# Stepper_CANBus_V2.net
KiCad netlist of a schematic drawn in EAGLE
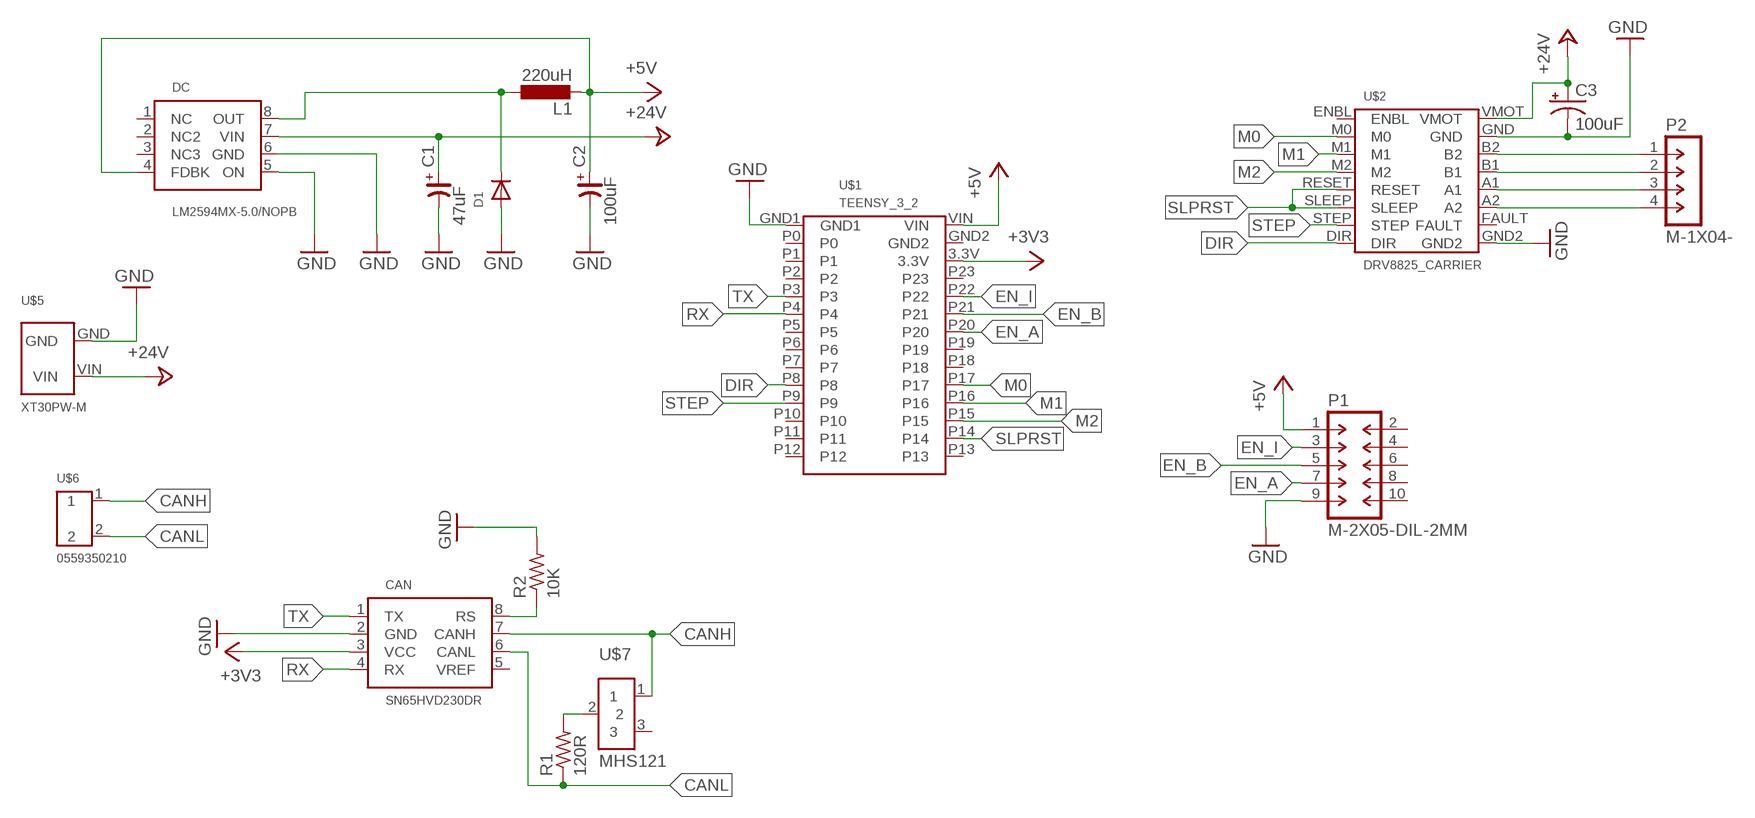
[diagram p0: schematic, sheet 1]

(export (version "E")
  (design (tool "Eeschema 10.0.6"))
  (components
    (comp (ref "C1")
      (value "47uF")
      (footprint "eagle-import:C7343_T")
      (libsource (lib "eagle-import") (part "CP_7343"))
    )
    (comp (ref "C2")
      (value "100uF")
      (footprint "eagle-import:C7343_T")
      (libsource (lib "eagle-import") (part "CP_7343"))
    )
    (comp (ref "C3")
      (value "100uF")
      (footprint "eagle-import:E2,5-7")
      (libsource (lib "eagle-import") (part "CPOL-USE2.5-7"))
    )
    (comp (ref "CAN")
      (value "SN65HVD230DR")
      (footprint "eagle-import:SOIC8")
      (libsource (lib "eagle-import") (part "SN65HVD230DR"))
    )
    (comp (ref "D1")
      (value "DIODESOD-323F")
      (footprint "eagle-import:SOD-323F")
      (libsource (lib "eagle-import") (part "DIODESOD-323F"))
    )
    (comp (ref "DC")
      (value "LM2594MX-5.0/NOPB")
      (footprint "eagle-import:SOIC8")
      (libsource (lib "eagle-import") (part "LM2594MX-5.0/NOPB"))
    )
    (comp (ref "L1")
      (value "220uH")
      (footprint "eagle-import:L4532M")
      (libsource (lib "eagle-import") (part "L-EUL4532C"))
    )
    (comp (ref "P1")
      (value "M-2X05-DIL-2MM")
      (footprint "eagle-import:DIL-2MM-2X05")
      (libsource (lib "eagle-import") (part "M-2X05-DIL-2MM"))
    )
    (comp (ref "P2")
      (value "M-1X04-")
      (footprint "eagle-import:DIL-2MM-1X04")
      (libsource (lib "eagle-import") (part "M-1X04-"))
    )
    (comp (ref "R1")
      (value "120R")
      (footprint "eagle-import:R0603")
      (libsource (lib "eagle-import") (part "R-US_R0603"))
    )
    (comp (ref "R2")
      (value "10K")
      (footprint "eagle-import:R0603")
      (libsource (lib "eagle-import") (part "R-US_R0603"))
    )
    (comp (ref "U$1")
      (value "TEENSY_3_2")
      (footprint "eagle-import:TEENSY_3_2")
      (libsource (lib "eagle-import") (part "TEENSY_3_2"))
    )
    (comp (ref "U$2")
      (value "DRV8825_CARRIER")
      (footprint "eagle-import:DRV8825_CARRIER")
      (libsource (lib "eagle-import") (part "DRV8825_CARRIER"))
    )
    (comp (ref "U$5")
      (value "XT30PW-M")
      (footprint "eagle-import:XT30PW-M")
      (libsource (lib "eagle-import") (part "XT30PW-M"))
    )
    (comp (ref "U$6")
      (value "0559350210")
      (footprint "eagle-import:0559350210")
      (libsource (lib "eagle-import") (part "0559350210"))
    )
    (comp (ref "U$7")
      (value "MHS121")
      (footprint "eagle-import:MHS121")
      (libsource (lib "eagle-import") (part "MHS121"))
    )
  )
  (nets
    (net (code "1") (name "+3V3") (class "Default")
      (node (ref "CAN") (pin "3") (pinfunction "VCC_3") (pintype "bidirectional"))
      (node (ref "U$1") (pin "3.3V") (pinfunction "3.3V_3.3V") (pintype "bidirectional"))
    )
    (net (code "2") (name "+5V") (class "Default")
      (node (ref "C2") (pin "+") (pinfunction "+_+") (pintype "passive"))
      (node (ref "DC") (pin "4") (pinfunction "FDBK_4") (pintype "bidirectional"))
      (node (ref "L1") (pin "2") (pinfunction "2_2") (pintype "passive"))
      (node (ref "P1") (pin "1") (pinfunction "1_1") (pintype "passive"))
      (node (ref "U$1") (pin "VIN") (pinfunction "VIN_VIN") (pintype "bidirectional"))
    )
    (net (code "3") (name "+24V") (class "Default")
      (node (ref "C1") (pin "+") (pinfunction "+_+") (pintype "passive"))
      (node (ref "C3") (pin "+") (pinfunction "+_+") (pintype "passive"))
      (node (ref "DC") (pin "7") (pinfunction "VIN_7") (pintype "bidirectional"))
      (node (ref "U$2") (pin "VMOT") (pinfunction "VMOT_VMOT") (pintype "bidirectional"))
      (node (ref "U$5") (pin "VIN") (pinfunction "VIN_VIN") (pintype "bidirectional"))
    )
    (net (code "4") (name "CANH") (class "Default")
      (node (ref "CAN") (pin "7") (pinfunction "CANH_7") (pintype "bidirectional"))
      (node (ref "U$6") (pin "1") (pinfunction "1_1") (pintype "bidirectional"))
      (node (ref "U$7") (pin "1") (pinfunction "1_1") (pintype "bidirectional"))
    )
    (net (code "5") (name "CANL") (class "Default")
      (node (ref "CAN") (pin "6") (pinfunction "CANL_6") (pintype "bidirectional"))
      (node (ref "R1") (pin "1") (pinfunction "1_1") (pintype "passive"))
      (node (ref "U$6") (pin "2") (pinfunction "2_2") (pintype "bidirectional"))
    )
    (net (code "6") (name "DIR") (class "Default")
      (node (ref "U$1") (pin "P8") (pinfunction "P8_P8") (pintype "bidirectional"))
      (node (ref "U$2") (pin "DIR") (pinfunction "DIR_DIR") (pintype "bidirectional"))
    )
    (net (code "7") (name "EN_A") (class "Default")
      (node (ref "P1") (pin "7") (pinfunction "7_7") (pintype "passive"))
      (node (ref "U$1") (pin "P20") (pinfunction "P20_P20") (pintype "bidirectional"))
    )
    (net (code "8") (name "EN_B") (class "Default")
      (node (ref "P1") (pin "5") (pinfunction "5_5") (pintype "passive"))
      (node (ref "U$1") (pin "P21") (pinfunction "P21_P21") (pintype "bidirectional"))
    )
    (net (code "9") (name "EN_I") (class "Default")
      (node (ref "P1") (pin "3") (pinfunction "3_3") (pintype "passive"))
      (node (ref "U$1") (pin "P22") (pinfunction "P22_P22") (pintype "bidirectional"))
    )
    (net (code "10") (name "GND") (class "Default")
      (node (ref "C1") (pin "-") (pinfunction "-_-") (pintype "passive"))
      (node (ref "C2") (pin "-") (pinfunction "-_-") (pintype "passive"))
      (node (ref "C3") (pin "-") (pinfunction "-_-") (pintype "passive"))
      (node (ref "CAN") (pin "2") (pinfunction "GND_2") (pintype "bidirectional"))
      (node (ref "D1") (pin "A") (pinfunction "A_A") (pintype "passive"))
      (node (ref "DC") (pin "5") (pinfunction "ON_5") (pintype "bidirectional"))
      (node (ref "DC") (pin "6") (pinfunction "GND_6") (pintype "bidirectional"))
      (node (ref "P1") (pin "9") (pinfunction "9_9") (pintype "passive"))
      (node (ref "R2") (pin "2") (pinfunction "2_2") (pintype "passive"))
      (node (ref "U$1") (pin "GND1") (pinfunction "GND1_GND1") (pintype "bidirectional"))
      (node (ref "U$2") (pin "GND") (pinfunction "GND_GND") (pintype "bidirectional"))
      (node (ref "U$2") (pin "GND2") (pinfunction "GND2_GND2") (pintype "bidirectional"))
      (node (ref "U$5") (pin "GND") (pinfunction "GND_GND") (pintype "bidirectional"))
    )
    (net (code "11") (name "M0") (class "Default")
      (node (ref "U$1") (pin "P17") (pinfunction "P17_P17") (pintype "bidirectional"))
      (node (ref "U$2") (pin "M0") (pinfunction "M0_M0") (pintype "bidirectional"))
    )
    (net (code "12") (name "M1") (class "Default")
      (node (ref "U$1") (pin "P16") (pinfunction "P16_P16") (pintype "bidirectional"))
      (node (ref "U$2") (pin "M1") (pinfunction "M1_M1") (pintype "bidirectional"))
    )
    (net (code "13") (name "M2") (class "Default")
      (node (ref "U$1") (pin "P15") (pinfunction "P15_P15") (pintype "bidirectional"))
      (node (ref "U$2") (pin "M2") (pinfunction "M2_M2") (pintype "bidirectional"))
    )
    (net (code "14") (name "Net-(CAN-RS)") (class "Default")
      (node (ref "CAN") (pin "8") (pinfunction "RS_8") (pintype "bidirectional"))
      (node (ref "R2") (pin "1") (pinfunction "1_1") (pintype "passive"))
    )
    (net (code "15") (name "Net-(DC-OUT)") (class "Default")
      (node (ref "D1") (pin "C") (pinfunction "C_C") (pintype "passive"))
      (node (ref "DC") (pin "8") (pinfunction "OUT_8") (pintype "bidirectional"))
      (node (ref "L1") (pin "1") (pinfunction "1_1") (pintype "passive"))
    )
    (net (code "16") (name "Net-(P2-Pad1)") (class "Default")
      (node (ref "P2") (pin "1") (pinfunction "1_1") (pintype "passive"))
      (node (ref "U$2") (pin "B2") (pinfunction "B2_B2") (pintype "bidirectional"))
    )
    (net (code "17") (name "Net-(P2-Pad2)") (class "Default")
      (node (ref "P2") (pin "2") (pinfunction "2_2") (pintype "passive"))
      (node (ref "U$2") (pin "B1") (pinfunction "B1_B1") (pintype "bidirectional"))
    )
    (net (code "18") (name "Net-(P2-Pad3)") (class "Default")
      (node (ref "P2") (pin "3") (pinfunction "3_3") (pintype "passive"))
      (node (ref "U$2") (pin "A1") (pinfunction "A1_A1") (pintype "bidirectional"))
    )
    (net (code "19") (name "Net-(P2-Pad4)") (class "Default")
      (node (ref "P2") (pin "4") (pinfunction "4_4") (pintype "passive"))
      (node (ref "U$2") (pin "A2") (pinfunction "A2_A2") (pintype "bidirectional"))
    )
    (net (code "20") (name "Net-(R1-Pad2)") (class "Default")
      (node (ref "R1") (pin "2") (pinfunction "2_2") (pintype "passive"))
      (node (ref "U$7") (pin "2") (pinfunction "2_2") (pintype "bidirectional"))
    )
    (net (code "21") (name "RX") (class "Default")
      (node (ref "CAN") (pin "4") (pinfunction "RX_4") (pintype "bidirectional"))
      (node (ref "U$1") (pin "P4") (pinfunction "P4_P4") (pintype "bidirectional"))
    )
    (net (code "22") (name "SLPRST") (class "Default")
      (node (ref "U$1") (pin "P14") (pinfunction "P14_P14") (pintype "bidirectional"))
      (node (ref "U$2") (pin "RESET") (pinfunction "RESET_RESET") (pintype "bidirectional"))
      (node (ref "U$2") (pin "SLEEP") (pinfunction "SLEEP_SLEEP") (pintype "bidirectional"))
    )
    (net (code "23") (name "STEP") (class "Default")
      (node (ref "U$1") (pin "P9") (pinfunction "P9_P9") (pintype "bidirectional"))
      (node (ref "U$2") (pin "STEP") (pinfunction "STEP_STEP") (pintype "bidirectional"))
    )
    (net (code "24") (name "TX") (class "Default")
      (node (ref "CAN") (pin "1") (pinfunction "TX_1") (pintype "bidirectional"))
      (node (ref "U$1") (pin "P3") (pinfunction "P3_P3") (pintype "bidirectional"))
    )
    (net (code "25") (name "unconnected-(CAN-VREF-Pad5)") (class "Default")
      (node (ref "CAN") (pin "5") (pinfunction "VREF_5") (pintype "bidirectional"))
    )
    (net (code "26") (name "unconnected-(DC-NC-Pad1)") (class "Default")
      (node (ref "DC") (pin "1") (pinfunction "NC_1") (pintype "bidirectional"))
    )
    (net (code "27") (name "unconnected-(DC-NC2-Pad2)") (class "Default")
      (node (ref "DC") (pin "2") (pinfunction "NC2_2") (pintype "bidirectional"))
    )
    (net (code "28") (name "unconnected-(DC-NC3-Pad3)") (class "Default")
      (node (ref "DC") (pin "3") (pinfunction "NC3_3") (pintype "bidirectional"))
    )
    (net (code "29") (name "unconnected-(P1-Pad2)") (class "Default")
      (node (ref "P1") (pin "2") (pinfunction "2_2") (pintype "passive"))
    )
    (net (code "30") (name "unconnected-(P1-Pad4)") (class "Default")
      (node (ref "P1") (pin "4") (pinfunction "4_4") (pintype "passive"))
    )
    (net (code "31") (name "unconnected-(P1-Pad6)") (class "Default")
      (node (ref "P1") (pin "6") (pinfunction "6_6") (pintype "passive"))
    )
    (net (code "32") (name "unconnected-(P1-Pad8)") (class "Default")
      (node (ref "P1") (pin "8") (pinfunction "8_8") (pintype "passive"))
    )
    (net (code "33") (name "unconnected-(P1-Pad10)") (class "Default")
      (node (ref "P1") (pin "10") (pinfunction "10_10") (pintype "passive"))
    )
    (net (code "34") (name "unconnected-(U$1-PadGND2)") (class "Default")
      (node (ref "U$1") (pin "GND2") (pinfunction "GND2_GND2") (pintype "bidirectional"))
    )
    (net (code "35") (name "unconnected-(U$1-PadP0)") (class "Default")
      (node (ref "U$1") (pin "P0") (pinfunction "P0_P0") (pintype "bidirectional"))
    )
    (net (code "36") (name "unconnected-(U$1-PadP1)") (class "Default")
      (node (ref "U$1") (pin "P1") (pinfunction "P1_P1") (pintype "bidirectional"))
    )
    (net (code "37") (name "unconnected-(U$1-PadP2)") (class "Default")
      (node (ref "U$1") (pin "P2") (pinfunction "P2_P2") (pintype "bidirectional"))
    )
    (net (code "38") (name "unconnected-(U$1-PadP5)") (class "Default")
      (node (ref "U$1") (pin "P5") (pinfunction "P5_P5") (pintype "bidirectional"))
    )
    (net (code "39") (name "unconnected-(U$1-PadP6)") (class "Default")
      (node (ref "U$1") (pin "P6") (pinfunction "P6_P6") (pintype "bidirectional"))
    )
    (net (code "40") (name "unconnected-(U$1-PadP7)") (class "Default")
      (node (ref "U$1") (pin "P7") (pinfunction "P7_P7") (pintype "bidirectional"))
    )
    (net (code "41") (name "unconnected-(U$1-PadP10)") (class "Default")
      (node (ref "U$1") (pin "P10") (pinfunction "P10_P10") (pintype "bidirectional"))
    )
    (net (code "42") (name "unconnected-(U$1-PadP11)") (class "Default")
      (node (ref "U$1") (pin "P11") (pinfunction "P11_P11") (pintype "bidirectional"))
    )
    (net (code "43") (name "unconnected-(U$1-PadP12)") (class "Default")
      (node (ref "U$1") (pin "P12") (pinfunction "P12_P12") (pintype "bidirectional"))
    )
    (net (code "44") (name "unconnected-(U$1-PadP13)") (class "Default")
      (node (ref "U$1") (pin "P13") (pinfunction "P13_P13") (pintype "bidirectional"))
    )
    (net (code "45") (name "unconnected-(U$1-PadP18)") (class "Default")
      (node (ref "U$1") (pin "P18") (pinfunction "P18_P18") (pintype "bidirectional"))
    )
    (net (code "46") (name "unconnected-(U$1-PadP19)") (class "Default")
      (node (ref "U$1") (pin "P19") (pinfunction "P19_P19") (pintype "bidirectional"))
    )
    (net (code "47") (name "unconnected-(U$1-PadP23)") (class "Default")
      (node (ref "U$1") (pin "P23") (pinfunction "P23_P23") (pintype "bidirectional"))
    )
    (net (code "48") (name "unconnected-(U$2-PadENBL)") (class "Default")
      (node (ref "U$2") (pin "ENBL") (pinfunction "ENBL_ENBL") (pintype "bidirectional"))
    )
    (net (code "49") (name "unconnected-(U$2-PadFAULT)") (class "Default")
      (node (ref "U$2") (pin "FAULT") (pinfunction "FAULT_FAULT") (pintype "bidirectional"))
    )
    (net (code "50") (name "unconnected-(U$7-Pad3)") (class "Default")
      (node (ref "U$7") (pin "3") (pinfunction "3_3") (pintype "bidirectional"))
    )
  )
)
